# board-v1.net
KiCad netlist of a schematic drawn in EAGLE
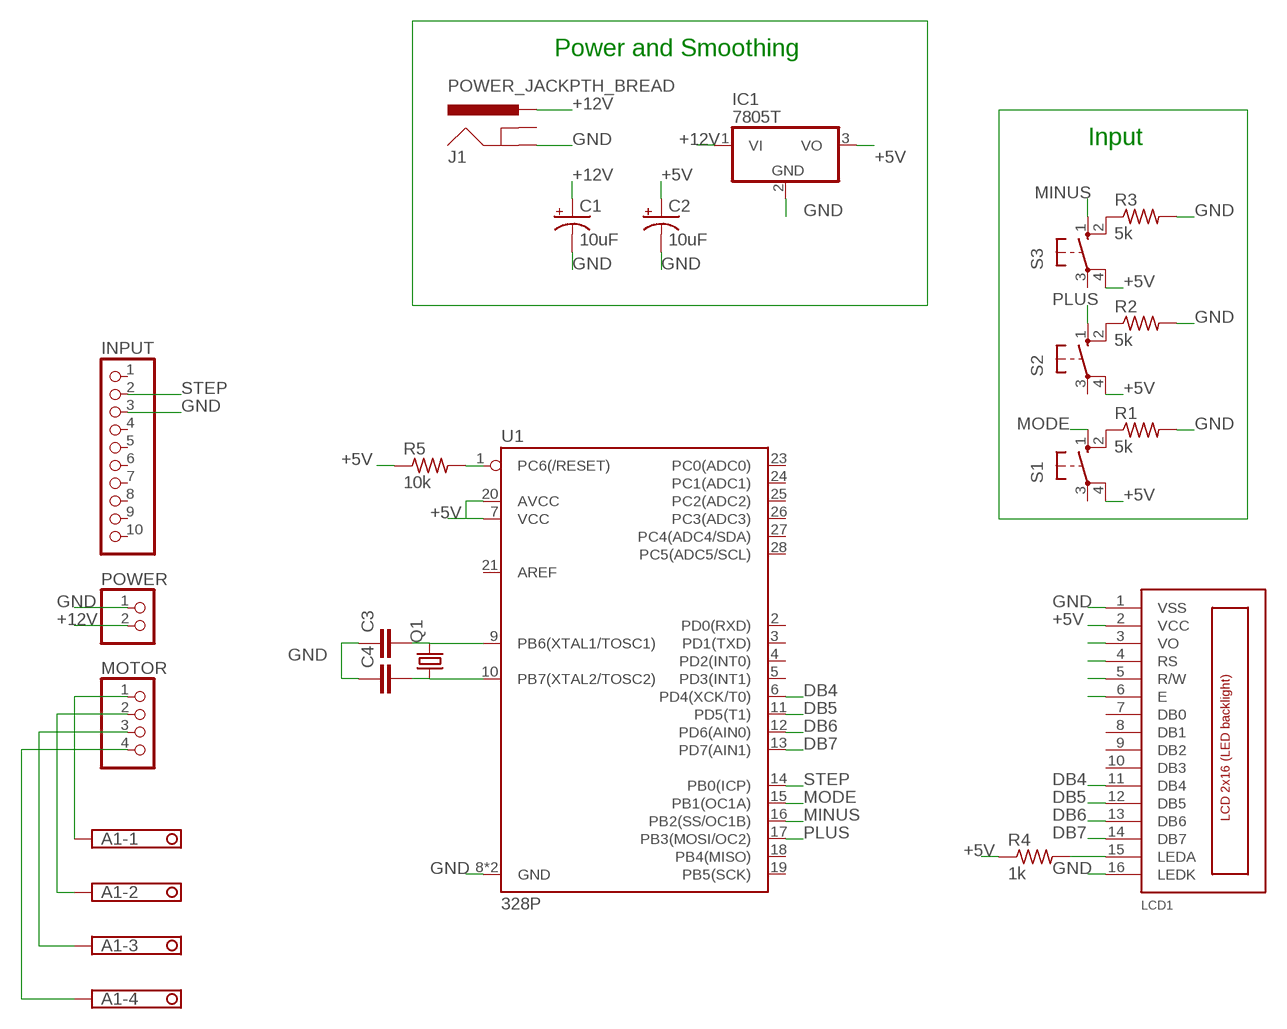
[diagram p0: schematic, sheet 1]

(export (version "E")
  (design (tool "Eeschema 10.0.6"))
  (components
    (comp (ref "A1")
      (value "TERMINAL-BLOCK-3.5MM-4-PIN-LONG-PAD")
      (footprint "eagle-import:TERMINAL-BLOCK-4-PIN-3.5MM-LONG-PAD")
      (libsource (lib "eagle-import") (part "TERMINAL-BLOCK-3.5MM-4-PIN-LONG-PAD"))
    )
    (comp (ref "C1")
      (value "10uF")
      (footprint "eagle-import:CPOL-RADIAL-2.5MM-5MM")
      (libsource (lib "eagle-import") (part "10UF-POLAR-RADIAL-2.5MM-25V-20%"))
    )
    (comp (ref "C2")
      (value "10uF")
      (footprint "eagle-import:CPOL-RADIAL-2.5MM-5MM")
      (libsource (lib "eagle-import") (part "10UF-POLAR-RADIAL-2.5MM-25V-20%"))
    )
    (comp (ref "C3")
      (value "C-EU025-024X044")
      (footprint "eagle-import:C025-024X044")
      (libsource (lib "eagle-import") (part "C-EU025-024X044"))
    )
    (comp (ref "C4")
      (value "C-EU025-024X044")
      (footprint "eagle-import:C025-024X044")
      (libsource (lib "eagle-import") (part "C-EU025-024X044"))
    )
    (comp (ref "IC1")
      (value "7805T")
      (footprint "eagle-import:TO220H")
      (libsource (lib "eagle-import") (part "78T05"))
    )
    (comp (ref "INPUT")
      (value "PINHD-1X10")
      (footprint "eagle-import:1X10")
      (libsource (lib "eagle-import") (part "PINHD-1X10"))
    )
    (comp (ref "J1")
      (value "POWER_JACKPTH_BREAD")
      (footprint "eagle-import:POWER_JACK_PTH_BREAD")
      (libsource (lib "eagle-import") (part "POWER_JACKPTH_BREAD"))
    )
    (comp (ref "LCD1")
      (value "LCD_2X16_SIL")
      (footprint "eagle-import:HY-1602F")
      (libsource (lib "eagle-import") (part "LCD_2X16_SIL"))
    )
    (comp (ref "MOTOR")
      (value "PINHD-1X4")
      (footprint "eagle-import:1X04")
      (libsource (lib "eagle-import") (part "PINHD-1X4"))
    )
    (comp (ref "POWER")
      (value "PINHD-1X2")
      (footprint "eagle-import:1X02")
      (libsource (lib "eagle-import") (part "PINHD-1X2"))
    )
    (comp (ref "Q1")
      (value "CRYSTALHC49S")
      (footprint "eagle-import:HC49_S")
      (libsource (lib "eagle-import") (part "CRYSTALHC49S"))
    )
    (comp (ref "R1")
      (value "5k")
      (footprint "eagle-import:0207_7")
      (libsource (lib "eagle-import") (part "R-US_0207/7"))
    )
    (comp (ref "R2")
      (value "5k")
      (footprint "eagle-import:0207_7")
      (libsource (lib "eagle-import") (part "R-US_0207/7"))
    )
    (comp (ref "R3")
      (value "5k")
      (footprint "eagle-import:0207_7")
      (libsource (lib "eagle-import") (part "R-US_0207/7"))
    )
    (comp (ref "R4")
      (value "1k")
      (footprint "eagle-import:0207_7")
      (libsource (lib "eagle-import") (part "R-US_0207/7"))
    )
    (comp (ref "R5")
      (value "10k")
      (footprint "eagle-import:0207_7")
      (libsource (lib "eagle-import") (part "R-US_0207/7"))
    )
    (comp (ref "S1")
      (value "40-XX")
      (footprint "eagle-import:B3F-40XX")
      (fields (field (name "MF") "OMRON COMPONENTS USA") (field (name "MPN") "B3F-4000"))
      (libsource (lib "eagle-import") (part "40-XX"))
    )
    (comp (ref "S2")
      (value "40-XX")
      (footprint "eagle-import:B3F-40XX")
      (fields (field (name "MF") "OMRON COMPONENTS USA") (field (name "MPN") "B3F-4000"))
      (libsource (lib "eagle-import") (part "40-XX"))
    )
    (comp (ref "S3")
      (value "40-XX")
      (footprint "eagle-import:B3F-40XX")
      (fields (field (name "MF") "OMRON COMPONENTS USA") (field (name "MPN") "B3F-4000"))
      (libsource (lib "eagle-import") (part "40-XX"))
    )
    (comp (ref "U1")
      (value "328P")
      (footprint "eagle-import:DIP28")
      (libsource (lib "eagle-import") (part "ATMEGA328P_PDIP"))
    )
  )
  (nets
    (net (code "1") (name "/+5V") (class "Default")
      (node (ref "C2") (pin "1") (pinfunction "+_1") (pintype "passive"))
      (node (ref "IC1") (pin "3") (pinfunction "VO_3") (pintype "passive"))
      (node (ref "LCD1") (pin "2") (pinfunction "VCC_2") (pintype "power_in"))
      (node (ref "R4") (pin "1") (pinfunction "1_1") (pintype "passive"))
      (node (ref "R5") (pin "1") (pinfunction "1_1") (pintype "passive"))
      (node (ref "S1") (pin "4") (pinfunction "P1_4") (pintype "passive"))
      (node (ref "S2") (pin "4") (pinfunction "P1_4") (pintype "passive"))
      (node (ref "S3") (pin "4") (pinfunction "P1_4") (pintype "passive"))
      (node (ref "U1") (pin "20") (pinfunction "AVCC_20") (pintype "bidirectional"))
      (node (ref "U1") (pin "7") (pinfunction "VCC_7") (pintype "bidirectional"))
    )
    (net (code "2") (name "/+12V") (class "Default")
      (node (ref "C1") (pin "1") (pinfunction "+_1") (pintype "passive"))
      (node (ref "IC1") (pin "1") (pinfunction "VI_1") (pintype "input"))
      (node (ref "J1") (pin "PWR") (pinfunction "PWR_PWR") (pintype "bidirectional"))
      (node (ref "POWER") (pin "2") (pinfunction "2_2") (pintype "passive"))
    )
    (net (code "3") (name "/DB4") (class "Default")
      (node (ref "LCD1") (pin "11") (pinfunction "DB4_11") (pintype "bidirectional"))
      (node (ref "U1") (pin "6") (pinfunction "PD4(XCK/T0)_6") (pintype "bidirectional"))
    )
    (net (code "4") (name "/DB5") (class "Default")
      (node (ref "LCD1") (pin "12") (pinfunction "DB5_12") (pintype "bidirectional"))
      (node (ref "U1") (pin "11") (pinfunction "PD5(T1)_11") (pintype "bidirectional"))
    )
    (net (code "5") (name "/DB6") (class "Default")
      (node (ref "LCD1") (pin "13") (pinfunction "DB6_13") (pintype "bidirectional"))
      (node (ref "U1") (pin "12") (pinfunction "PD6(AIN0)_12") (pintype "bidirectional"))
    )
    (net (code "6") (name "/DB7") (class "Default")
      (node (ref "LCD1") (pin "14") (pinfunction "DB7_14") (pintype "bidirectional"))
      (node (ref "U1") (pin "13") (pinfunction "PD7(AIN1)_13") (pintype "bidirectional"))
    )
    (net (code "7") (name "/GND") (class "Default")
      (node (ref "C1") (pin "2") (pinfunction "-_2") (pintype "passive"))
      (node (ref "C2") (pin "2") (pinfunction "-_2") (pintype "passive"))
      (node (ref "C3") (pin "1") (pinfunction "1_1") (pintype "passive"))
      (node (ref "C4") (pin "1") (pinfunction "1_1") (pintype "passive"))
      (node (ref "IC1") (pin "2") (pinfunction "GND_2") (pintype "passive"))
      (node (ref "INPUT") (pin "3") (pinfunction "3_3") (pintype "passive"))
      (node (ref "J1") (pin "GND") (pinfunction "GND_GND") (pintype "bidirectional"))
      (node (ref "LCD1") (pin "1") (pinfunction "VSS_1") (pintype "power_in"))
      (node (ref "LCD1") (pin "16") (pinfunction "LEDK_16") (pintype "passive"))
      (node (ref "POWER") (pin "1") (pinfunction "1_1") (pintype "passive"))
      (node (ref "R1") (pin "2") (pinfunction "2_2") (pintype "passive"))
      (node (ref "R2") (pin "2") (pinfunction "2_2") (pintype "passive"))
      (node (ref "R3") (pin "2") (pinfunction "2_2") (pintype "passive"))
      (node (ref "U1") (pin "22") (pinfunction "GND_22") (pintype "bidirectional"))
      (node (ref "U1") (pin "8") (pinfunction "GND_8") (pintype "bidirectional"))
    )
    (net (code "8") (name "/MINUS") (class "Default")
      (node (ref "S3") (pin "1") (pinfunction "S_1") (pintype "passive"))
      (node (ref "U1") (pin "16") (pinfunction "PB2(SS/OC1B)_16") (pintype "bidirectional"))
    )
    (net (code "9") (name "/MODE") (class "Default")
      (node (ref "S1") (pin "1") (pinfunction "S_1") (pintype "passive"))
      (node (ref "U1") (pin "15") (pinfunction "PB1(OC1A)_15") (pintype "bidirectional"))
    )
    (net (code "10") (name "/PLUS") (class "Default")
      (node (ref "S2") (pin "1") (pinfunction "S_1") (pintype "passive"))
      (node (ref "U1") (pin "17") (pinfunction "PB3(MOSI/OC2)_17") (pintype "bidirectional"))
    )
    (net (code "11") (name "/STEP") (class "Default")
      (node (ref "INPUT") (pin "2") (pinfunction "2_2") (pintype "passive"))
      (node (ref "U1") (pin "14") (pinfunction "PB0(ICP)_14") (pintype "bidirectional"))
    )
    (net (code "12") (name "Net-(A1A-K)") (class "Default")
      (node (ref "A1") (pin "1") (pinfunction "K_1") (pintype "passive"))
      (node (ref "MOTOR") (pin "1") (pinfunction "1_1") (pintype "passive"))
    )
    (net (code "13") (name "Net-(A1B-K)") (class "Default")
      (node (ref "A1") (pin "2") (pinfunction "K_2") (pintype "passive"))
      (node (ref "MOTOR") (pin "2") (pinfunction "2_2") (pintype "passive"))
    )
    (net (code "14") (name "Net-(A1C-K)") (class "Default")
      (node (ref "A1") (pin "3") (pinfunction "K_3") (pintype "passive"))
      (node (ref "MOTOR") (pin "3") (pinfunction "3_3") (pintype "passive"))
    )
    (net (code "15") (name "Net-(A1D-K)") (class "Default")
      (node (ref "A1") (pin "4") (pinfunction "K_4") (pintype "passive"))
      (node (ref "MOTOR") (pin "4") (pinfunction "4_4") (pintype "passive"))
    )
    (net (code "16") (name "Net-(LCD1-LEDA)") (class "Default")
      (node (ref "LCD1") (pin "15") (pinfunction "LEDA_15") (pintype "passive"))
      (node (ref "R4") (pin "2") (pinfunction "2_2") (pintype "passive"))
    )
    (net (code "17") (name "Net-(S1-S1)") (class "Default")
      (node (ref "R1") (pin "1") (pinfunction "1_1") (pintype "passive"))
      (node (ref "S1") (pin "2") (pinfunction "S1_2") (pintype "passive"))
    )
    (net (code "18") (name "Net-(S2-S1)") (class "Default")
      (node (ref "R2") (pin "1") (pinfunction "1_1") (pintype "passive"))
      (node (ref "S2") (pin "2") (pinfunction "S1_2") (pintype "passive"))
    )
    (net (code "19") (name "Net-(S3-S1)") (class "Default")
      (node (ref "R3") (pin "1") (pinfunction "1_1") (pintype "passive"))
      (node (ref "S3") (pin "2") (pinfunction "S1_2") (pintype "passive"))
    )
    (net (code "20") (name "Net-(U1-PB6(XTAL1{slash}TOSC1))") (class "Default")
      (node (ref "C3") (pin "2") (pinfunction "2_2") (pintype "passive"))
      (node (ref "Q1") (pin "2") (pinfunction "2_2") (pintype "passive"))
      (node (ref "U1") (pin "9") (pinfunction "PB6(XTAL1/TOSC1)_9") (pintype "bidirectional"))
    )
    (net (code "21") (name "Net-(U1-PB7(XTAL2{slash}TOSC2))") (class "Default")
      (node (ref "C4") (pin "2") (pinfunction "2_2") (pintype "passive"))
      (node (ref "Q1") (pin "1") (pinfunction "1_1") (pintype "passive"))
      (node (ref "U1") (pin "10") (pinfunction "PB7(XTAL2/TOSC2)_10") (pintype "bidirectional"))
    )
    (net (code "22") (name "Net-(U1-PC6({slash}RESET))") (class "Default")
      (node (ref "R5") (pin "2") (pinfunction "2_2") (pintype "passive"))
      (node (ref "U1") (pin "1") (pinfunction "PC6(/RESET)_1") (pintype "bidirectional"))
    )
    (net (code "23") (name "unconnected-(INPUT-Pad1)") (class "Default")
      (node (ref "INPUT") (pin "1") (pinfunction "1_1") (pintype "passive"))
    )
    (net (code "24") (name "unconnected-(INPUT-Pad4)") (class "Default")
      (node (ref "INPUT") (pin "4") (pinfunction "4_4") (pintype "passive"))
    )
    (net (code "25") (name "unconnected-(INPUT-Pad5)") (class "Default")
      (node (ref "INPUT") (pin "5") (pinfunction "5_5") (pintype "passive"))
    )
    (net (code "26") (name "unconnected-(INPUT-Pad6)") (class "Default")
      (node (ref "INPUT") (pin "6") (pinfunction "6_6") (pintype "passive"))
    )
    (net (code "27") (name "unconnected-(INPUT-Pad7)") (class "Default")
      (node (ref "INPUT") (pin "7") (pinfunction "7_7") (pintype "passive"))
    )
    (net (code "28") (name "unconnected-(INPUT-Pad8)") (class "Default")
      (node (ref "INPUT") (pin "8") (pinfunction "8_8") (pintype "passive"))
    )
    (net (code "29") (name "unconnected-(INPUT-Pad9)") (class "Default")
      (node (ref "INPUT") (pin "9") (pinfunction "9_9") (pintype "passive"))
    )
    (net (code "30") (name "unconnected-(INPUT-Pad10)") (class "Default")
      (node (ref "INPUT") (pin "10") (pinfunction "10_10") (pintype "passive"))
    )
    (net (code "31") (name "unconnected-(J1-PadGNDBREAK)") (class "Default")
      (node (ref "J1") (pin "GNDBREAK") (pinfunction "GNDBREAK_GNDBREAK") (pintype "bidirectional"))
    )
    (net (code "32") (name "unconnected-(LCD1-DB0-Pad7)") (class "Default")
      (node (ref "LCD1") (pin "7") (pinfunction "DB0_7") (pintype "bidirectional"))
    )
    (net (code "33") (name "unconnected-(LCD1-DB1-Pad8)") (class "Default")
      (node (ref "LCD1") (pin "8") (pinfunction "DB1_8") (pintype "bidirectional"))
    )
    (net (code "34") (name "unconnected-(LCD1-DB2-Pad9)") (class "Default")
      (node (ref "LCD1") (pin "9") (pinfunction "DB2_9") (pintype "bidirectional"))
    )
    (net (code "35") (name "unconnected-(LCD1-DB3-Pad10)") (class "Default")
      (node (ref "LCD1") (pin "10") (pinfunction "DB3_10") (pintype "bidirectional"))
    )
    (net (code "36") (name "unconnected-(LCD1-E-Pad6)") (class "Default")
      (node (ref "LCD1") (pin "6") (pinfunction "E_6") (pintype "input"))
    )
    (net (code "37") (name "unconnected-(LCD1-RS-Pad4)") (class "Default")
      (node (ref "LCD1") (pin "4") (pinfunction "RS_4") (pintype "input"))
    )
    (net (code "38") (name "unconnected-(LCD1-R{slash}W-Pad5)") (class "Default")
      (node (ref "LCD1") (pin "5") (pinfunction "R/W_5") (pintype "input"))
    )
    (net (code "39") (name "unconnected-(LCD1-VO-Pad3)") (class "Default")
      (node (ref "LCD1") (pin "3") (pinfunction "VO_3") (pintype "input"))
    )
    (net (code "40") (name "unconnected-(S1-P-Pad3)") (class "Default")
      (node (ref "S1") (pin "3") (pinfunction "P_3") (pintype "passive"))
    )
    (net (code "41") (name "unconnected-(S2-P-Pad3)") (class "Default")
      (node (ref "S2") (pin "3") (pinfunction "P_3") (pintype "passive"))
    )
    (net (code "42") (name "unconnected-(S3-P-Pad3)") (class "Default")
      (node (ref "S3") (pin "3") (pinfunction "P_3") (pintype "passive"))
    )
    (net (code "43") (name "unconnected-(U1-AREF-Pad21)") (class "Default")
      (node (ref "U1") (pin "21") (pinfunction "AREF_21") (pintype "bidirectional"))
    )
    (net (code "44") (name "unconnected-(U1-PB4(MISO)-Pad18)") (class "Default")
      (node (ref "U1") (pin "18") (pinfunction "PB4(MISO)_18") (pintype "bidirectional"))
    )
    (net (code "45") (name "unconnected-(U1-PB5(SCK)-Pad19)") (class "Default")
      (node (ref "U1") (pin "19") (pinfunction "PB5(SCK)_19") (pintype "bidirectional"))
    )
    (net (code "46") (name "unconnected-(U1-PC0(ADC0)-Pad23)") (class "Default")
      (node (ref "U1") (pin "23") (pinfunction "PC0(ADC0)_23") (pintype "bidirectional"))
    )
    (net (code "47") (name "unconnected-(U1-PC1(ADC1)-Pad24)") (class "Default")
      (node (ref "U1") (pin "24") (pinfunction "PC1(ADC1)_24") (pintype "bidirectional"))
    )
    (net (code "48") (name "unconnected-(U1-PC2(ADC2)-Pad25)") (class "Default")
      (node (ref "U1") (pin "25") (pinfunction "PC2(ADC2)_25") (pintype "bidirectional"))
    )
    (net (code "49") (name "unconnected-(U1-PC3(ADC3)-Pad26)") (class "Default")
      (node (ref "U1") (pin "26") (pinfunction "PC3(ADC3)_26") (pintype "bidirectional"))
    )
    (net (code "50") (name "unconnected-(U1-PC4(ADC4{slash}SDA)-Pad27)") (class "Default")
      (node (ref "U1") (pin "27") (pinfunction "PC4(ADC4/SDA)_27") (pintype "bidirectional"))
    )
    (net (code "51") (name "unconnected-(U1-PC5(ADC5{slash}SCL)-Pad28)") (class "Default")
      (node (ref "U1") (pin "28") (pinfunction "PC5(ADC5/SCL)_28") (pintype "bidirectional"))
    )
    (net (code "52") (name "unconnected-(U1-PD0(RXD)-Pad2)") (class "Default")
      (node (ref "U1") (pin "2") (pinfunction "PD0(RXD)_2") (pintype "bidirectional"))
    )
    (net (code "53") (name "unconnected-(U1-PD1(TXD)-Pad3)") (class "Default")
      (node (ref "U1") (pin "3") (pinfunction "PD1(TXD)_3") (pintype "bidirectional"))
    )
    (net (code "54") (name "unconnected-(U1-PD2(INT0)-Pad4)") (class "Default")
      (node (ref "U1") (pin "4") (pinfunction "PD2(INT0)_4") (pintype "bidirectional"))
    )
    (net (code "55") (name "unconnected-(U1-PD3(INT1)-Pad5)") (class "Default")
      (node (ref "U1") (pin "5") (pinfunction "PD3(INT1)_5") (pintype "bidirectional"))
    )
  )
)
